# 7seg.net
KiCad netlist of a schematic drawn in EAGLE
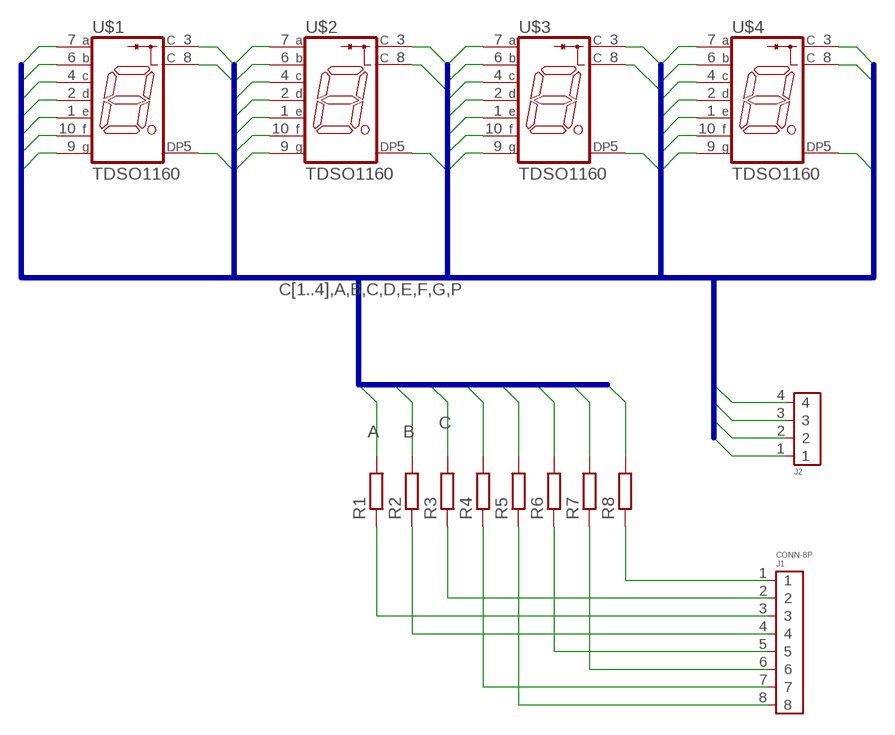
[diagram p0: schematic, sheet 1]

(export (version "E")
  (design (tool "Eeschema 10.0.6"))
  (components
    (comp (ref "J1")
      (value "CONN-8P")
      (footprint "eagle-import:CONN-8P")
      (libsource (lib "eagle-import") (part "CONN-8P"))
    )
    (comp (ref "J2")
      (value "CONN-4P-4P")
      (footprint "eagle-import:CONN-4P")
      (libsource (lib "eagle-import") (part "CONN-4P-4P"))
    )
    (comp (ref "R1")
      (value "R0202/7-V")
      (footprint "eagle-import:0202_7-V")
      (libsource (lib "eagle-import") (part "R0202/7-V"))
    )
    (comp (ref "R2")
      (value "R0202/7-V")
      (footprint "eagle-import:0202_7-V")
      (libsource (lib "eagle-import") (part "R0202/7-V"))
    )
    (comp (ref "R3")
      (value "R0202/7-V")
      (footprint "eagle-import:0202_7-V")
      (libsource (lib "eagle-import") (part "R0202/7-V"))
    )
    (comp (ref "R4")
      (value "R0202/7-V")
      (footprint "eagle-import:0202_7-V")
      (libsource (lib "eagle-import") (part "R0202/7-V"))
    )
    (comp (ref "R5")
      (value "R0202/7-V")
      (footprint "eagle-import:0202_7-V")
      (libsource (lib "eagle-import") (part "R0202/7-V"))
    )
    (comp (ref "R6")
      (value "R0202/7-V")
      (footprint "eagle-import:0202_7-V")
      (libsource (lib "eagle-import") (part "R0202/7-V"))
    )
    (comp (ref "R7")
      (value "R0202/7-V")
      (footprint "eagle-import:0202_7-V")
      (libsource (lib "eagle-import") (part "R0202/7-V"))
    )
    (comp (ref "R8")
      (value "R0202/7-V")
      (footprint "eagle-import:0202_7-V")
      (libsource (lib "eagle-import") (part "R0202/7-V"))
    )
    (comp (ref "U$1")
      (value "TDSO1160")
      (footprint "eagle-import:TDSX1150")
      (libsource (lib "eagle-import") (part "TDSO1160"))
    )
    (comp (ref "U$2")
      (value "TDSO1160")
      (footprint "eagle-import:TDSX1150")
      (libsource (lib "eagle-import") (part "TDSO1160"))
    )
    (comp (ref "U$3")
      (value "TDSO1160")
      (footprint "eagle-import:TDSX1150")
      (libsource (lib "eagle-import") (part "TDSO1160"))
    )
    (comp (ref "U$4")
      (value "TDSO1160")
      (footprint "eagle-import:TDSX1150")
      (libsource (lib "eagle-import") (part "TDSO1160"))
    )
  )
  (nets
    (net (code "1") (name "/A") (class "Default")
      (node (ref "R1") (pin "2") (pinfunction "2_2") (pintype "passive"))
      (node (ref "U$1") (pin "7") (pinfunction "A_7") (pintype "passive"))
      (node (ref "U$2") (pin "7") (pinfunction "A_7") (pintype "passive"))
      (node (ref "U$3") (pin "7") (pinfunction "A_7") (pintype "passive"))
      (node (ref "U$4") (pin "7") (pinfunction "A_7") (pintype "passive"))
    )
    (net (code "2") (name "/B") (class "Default")
      (node (ref "R2") (pin "2") (pinfunction "2_2") (pintype "passive"))
      (node (ref "U$1") (pin "6") (pinfunction "B_6") (pintype "passive"))
      (node (ref "U$2") (pin "6") (pinfunction "B_6") (pintype "passive"))
      (node (ref "U$3") (pin "6") (pinfunction "B_6") (pintype "passive"))
      (node (ref "U$4") (pin "6") (pinfunction "B_6") (pintype "passive"))
    )
    (net (code "3") (name "/C") (class "Default")
      (node (ref "R3") (pin "2") (pinfunction "2_2") (pintype "passive"))
      (node (ref "U$1") (pin "4") (pinfunction "C_4") (pintype "passive"))
      (node (ref "U$2") (pin "4") (pinfunction "C_4") (pintype "passive"))
      (node (ref "U$3") (pin "4") (pinfunction "C_4") (pintype "passive"))
      (node (ref "U$4") (pin "4") (pinfunction "C_4") (pintype "passive"))
    )
    (net (code "4") (name "/C1") (class "Default")
      (node (ref "J2") (pin "1") (pinfunction "1_1") (pintype "bidirectional"))
      (node (ref "U$1") (pin "3") (pinfunction "C_3") (pintype "passive"))
      (node (ref "U$1") (pin "8") (pinfunction "C_8") (pintype "passive"))
    )
    (net (code "5") (name "/C2") (class "Default")
      (node (ref "J2") (pin "2") (pinfunction "2_2") (pintype "bidirectional"))
      (node (ref "U$2") (pin "3") (pinfunction "C_3") (pintype "passive"))
      (node (ref "U$2") (pin "8") (pinfunction "C_8") (pintype "passive"))
    )
    (net (code "6") (name "/C3") (class "Default")
      (node (ref "J2") (pin "3") (pinfunction "3_3") (pintype "bidirectional"))
      (node (ref "U$3") (pin "3") (pinfunction "C_3") (pintype "passive"))
      (node (ref "U$3") (pin "8") (pinfunction "C_8") (pintype "passive"))
    )
    (net (code "7") (name "/C4") (class "Default")
      (node (ref "J2") (pin "4") (pinfunction "4_4") (pintype "bidirectional"))
      (node (ref "U$4") (pin "3") (pinfunction "C_3") (pintype "passive"))
      (node (ref "U$4") (pin "8") (pinfunction "C_8") (pintype "passive"))
    )
    (net (code "8") (name "/D") (class "Default")
      (node (ref "R4") (pin "2") (pinfunction "2_2") (pintype "passive"))
      (node (ref "U$1") (pin "2") (pinfunction "D_2") (pintype "passive"))
      (node (ref "U$2") (pin "2") (pinfunction "D_2") (pintype "passive"))
      (node (ref "U$3") (pin "2") (pinfunction "D_2") (pintype "passive"))
      (node (ref "U$4") (pin "2") (pinfunction "D_2") (pintype "passive"))
    )
    (net (code "9") (name "/E") (class "Default")
      (node (ref "R5") (pin "2") (pinfunction "2_2") (pintype "passive"))
      (node (ref "U$1") (pin "1") (pinfunction "E_1") (pintype "passive"))
      (node (ref "U$2") (pin "1") (pinfunction "E_1") (pintype "passive"))
      (node (ref "U$3") (pin "1") (pinfunction "E_1") (pintype "passive"))
      (node (ref "U$4") (pin "1") (pinfunction "E_1") (pintype "passive"))
    )
    (net (code "10") (name "/F") (class "Default")
      (node (ref "R6") (pin "2") (pinfunction "2_2") (pintype "passive"))
      (node (ref "U$1") (pin "10") (pinfunction "F_10") (pintype "passive"))
      (node (ref "U$2") (pin "10") (pinfunction "F_10") (pintype "passive"))
      (node (ref "U$3") (pin "10") (pinfunction "F_10") (pintype "passive"))
      (node (ref "U$4") (pin "10") (pinfunction "F_10") (pintype "passive"))
    )
    (net (code "11") (name "/G") (class "Default")
      (node (ref "R7") (pin "2") (pinfunction "2_2") (pintype "passive"))
      (node (ref "U$1") (pin "9") (pinfunction "G_9") (pintype "passive"))
      (node (ref "U$2") (pin "9") (pinfunction "G_9") (pintype "passive"))
      (node (ref "U$3") (pin "9") (pinfunction "G_9") (pintype "passive"))
      (node (ref "U$4") (pin "9") (pinfunction "G_9") (pintype "passive"))
    )
    (net (code "12") (name "/P") (class "Default")
      (node (ref "R8") (pin "2") (pinfunction "2_2") (pintype "passive"))
      (node (ref "U$1") (pin "5") (pinfunction "DP_5") (pintype "passive"))
      (node (ref "U$2") (pin "5") (pinfunction "DP_5") (pintype "passive"))
      (node (ref "U$3") (pin "5") (pinfunction "DP_5") (pintype "passive"))
      (node (ref "U$4") (pin "5") (pinfunction "DP_5") (pintype "passive"))
    )
    (net (code "14") (name "Net-(J1-Pad1)") (class "Default")
      (node (ref "J1") (pin "1") (pinfunction "1_1") (pintype "passive"))
      (node (ref "R8") (pin "1") (pinfunction "1_1") (pintype "passive"))
    )
    (net (code "15") (name "Net-(J1-Pad2)") (class "Default")
      (node (ref "J1") (pin "2") (pinfunction "2_2") (pintype "passive"))
      (node (ref "R3") (pin "1") (pinfunction "1_1") (pintype "passive"))
    )
    (net (code "16") (name "Net-(J1-Pad3)") (class "Default")
      (node (ref "J1") (pin "3") (pinfunction "3_3") (pintype "passive"))
      (node (ref "R1") (pin "1") (pinfunction "1_1") (pintype "passive"))
    )
    (net (code "17") (name "Net-(J1-Pad4)") (class "Default")
      (node (ref "J1") (pin "4") (pinfunction "4_4") (pintype "passive"))
      (node (ref "R2") (pin "1") (pinfunction "1_1") (pintype "passive"))
    )
    (net (code "18") (name "Net-(J1-Pad5)") (class "Default")
      (node (ref "J1") (pin "5") (pinfunction "5_5") (pintype "passive"))
      (node (ref "R6") (pin "1") (pinfunction "1_1") (pintype "passive"))
    )
    (net (code "19") (name "Net-(J1-Pad6)") (class "Default")
      (node (ref "J1") (pin "6") (pinfunction "6_6") (pintype "passive"))
      (node (ref "R7") (pin "1") (pinfunction "1_1") (pintype "passive"))
    )
    (net (code "20") (name "Net-(J1-Pad7)") (class "Default")
      (node (ref "J1") (pin "7") (pinfunction "7_7") (pintype "passive"))
      (node (ref "R4") (pin "1") (pinfunction "1_1") (pintype "passive"))
    )
    (net (code "21") (name "Net-(J1-Pad8)") (class "Default")
      (node (ref "J1") (pin "8") (pinfunction "8_8") (pintype "passive"))
      (node (ref "R5") (pin "1") (pinfunction "1_1") (pintype "passive"))
    )
  )
)
